# ESP32-C3_V01.net
KiCad netlist of a schematic drawn in Altium Designer
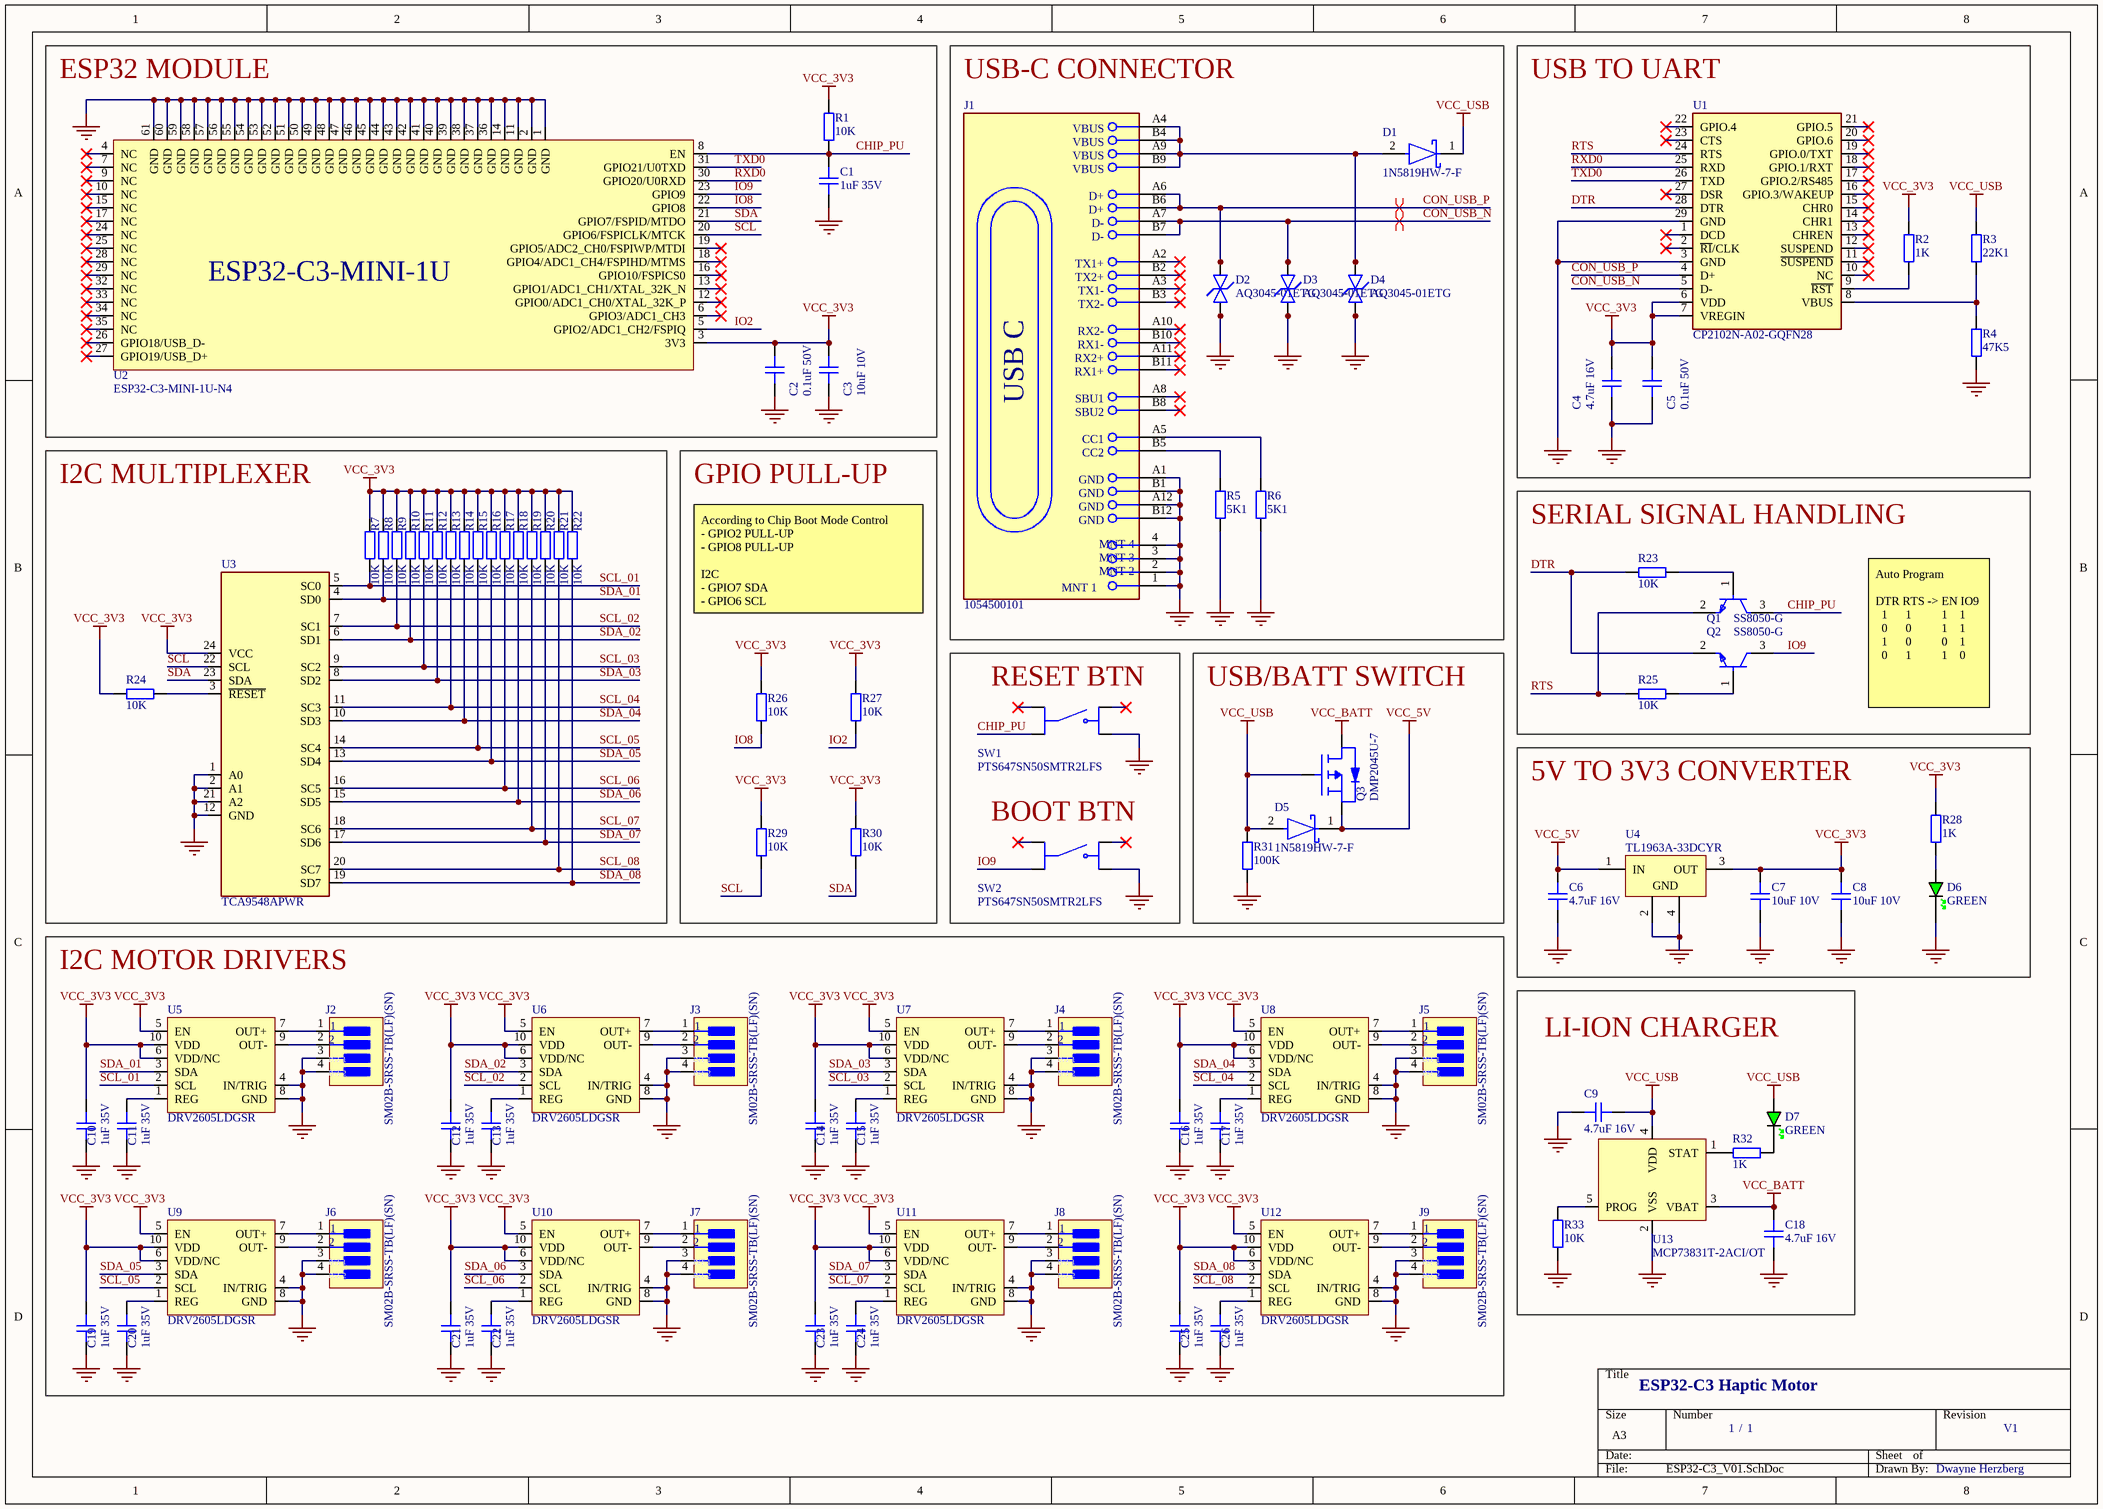
[diagram p0: ESP32-C3_V01.SchDoc]

(export (version "E")
  (design (tool "Eeschema 10.0.6"))
  (components
    (comp (ref "C1")
      (value "1uF 35V")
      (footprint "CAP_0402")
      (description "CAP CER 1UF 35V X5R 0402")
      (fields
        (field (name "MANUFACTURER") "Samsung")
        (field (name "MANUFACTURER PART NUMBER") "CL05A105KL5NRNC")
      )
      (libsource (lib "ESP32-C3") (part "CL05A105KL5NRNC"))
    )
    (comp (ref "C2")
      (value "0.1uF 50V")
      (footprint "CAP_0402")
      (description "CAP CER 0.1UF 50V X7R 0402")
      (fields
        (field (name "MANUFACTURER") "Samsung")
        (field (name "MANUFACTURER PART NUMBER") "CL05B104KB54PNC")
      )
      (libsource (lib "ESP32-C3") (part "CL05B104KB54PNC"))
    )
    (comp (ref "C3")
      (value "10uF 10V")
      (footprint "CAP_0402")
      (description "CAP CER 10UF 10V X5R 0402")
      (fields
        (field (name "MANUFACTURER") "Samsung")
        (field (name "MANUFACTURER PART NUMBER") "CL05A106MP8NUB8")
      )
      (libsource (lib "ESP32-C3") (part "CL05A106MP8NUB8"))
    )
    (comp (ref "C4")
      (value "4.7uF 16V")
      (footprint "CAP_0402")
      (description "CAP CER 4.7UF 16V X5R 0402")
      (fields
        (field (name "MANUFACTURER") "Samsung")
        (field (name "MANUFACTURER PART NUMBER") "CL05A475MO5NUNC")
      )
      (libsource (lib "ESP32-C3") (part "CL05A475MO5NUNC"))
    )
    (comp (ref "C5")
      (value "0.1uF 50V")
      (footprint "CAP_0402")
      (description "CAP CER 0.1UF 50V X7R 0402")
      (fields
        (field (name "MANUFACTURER") "Samsung")
        (field (name "MANUFACTURER PART NUMBER") "CL05B104KB54PNC")
      )
      (libsource (lib "ESP32-C3") (part "CL05B104KB54PNC"))
    )
    (comp (ref "C6")
      (value "4.7uF 16V")
      (footprint "CAP_0402")
      (description "CAP CER 4.7UF 16V X5R 0402")
      (fields
        (field (name "MANUFACTURER") "Samsung")
        (field (name "MANUFACTURER PART NUMBER") "CL05A475MO5NUNC")
      )
      (libsource (lib "ESP32-C3") (part "CL05A475MO5NUNC"))
    )
    (comp (ref "C7")
      (value "10uF 10V")
      (footprint "CAP_0402")
      (description "CAP CER 10UF 10V X5R 0402")
      (fields
        (field (name "MANUFACTURER") "Samsung")
        (field (name "MANUFACTURER PART NUMBER") "CL05A106MP8NUB8")
      )
      (libsource (lib "ESP32-C3") (part "CL05A106MP8NUB8"))
    )
    (comp (ref "C8")
      (value "10uF 10V")
      (footprint "CAP_0402")
      (description "CAP CER 10UF 10V X5R 0402")
      (fields
        (field (name "MANUFACTURER") "Samsung")
        (field (name "MANUFACTURER PART NUMBER") "CL05A106MP8NUB8")
      )
      (libsource (lib "ESP32-C3") (part "CL05A106MP8NUB8"))
    )
    (comp (ref "C9")
      (value "4.7uF 16V")
      (footprint "CAP_0402")
      (description "CAP CER 4.7UF 16V X5R 0402")
      (fields
        (field (name "MANUFACTURER") "Samsung")
        (field (name "MANUFACTURER PART NUMBER") "CL05A475MO5NUNC")
      )
      (libsource (lib "ESP32-C3") (part "CL05A475MO5NUNC"))
    )
    (comp (ref "C10")
      (value "1uF 35V")
      (footprint "CAP_0402")
      (description "CAP CER 1UF 35V X5R 0402")
      (fields
        (field (name "MANUFACTURER") "Samsung")
        (field (name "MANUFACTURER PART NUMBER") "CL05A105KL5NRNC")
      )
      (libsource (lib "ESP32-C3") (part "CL05A105KL5NRNC"))
    )
    (comp (ref "C11")
      (value "1uF 35V")
      (footprint "CAP_0402")
      (description "CAP CER 1UF 35V X5R 0402")
      (fields
        (field (name "MANUFACTURER") "Samsung")
        (field (name "MANUFACTURER PART NUMBER") "CL05A105KL5NRNC")
      )
      (libsource (lib "ESP32-C3") (part "CL05A105KL5NRNC"))
    )
    (comp (ref "C12")
      (value "1uF 35V")
      (footprint "CAP_0402")
      (description "CAP CER 1UF 35V X5R 0402")
      (fields
        (field (name "MANUFACTURER") "Samsung")
        (field (name "MANUFACTURER PART NUMBER") "CL05A105KL5NRNC")
      )
      (libsource (lib "ESP32-C3") (part "CL05A105KL5NRNC"))
    )
    (comp (ref "C13")
      (value "1uF 35V")
      (footprint "CAP_0402")
      (description "CAP CER 1UF 35V X5R 0402")
      (fields
        (field (name "MANUFACTURER") "Samsung")
        (field (name "MANUFACTURER PART NUMBER") "CL05A105KL5NRNC")
      )
      (libsource (lib "ESP32-C3") (part "CL05A105KL5NRNC"))
    )
    (comp (ref "C14")
      (value "1uF 35V")
      (footprint "CAP_0402")
      (description "CAP CER 1UF 35V X5R 0402")
      (fields
        (field (name "MANUFACTURER") "Samsung")
        (field (name "MANUFACTURER PART NUMBER") "CL05A105KL5NRNC")
      )
      (libsource (lib "ESP32-C3") (part "CL05A105KL5NRNC"))
    )
    (comp (ref "C15")
      (value "1uF 35V")
      (footprint "CAP_0402")
      (description "CAP CER 1UF 35V X5R 0402")
      (fields
        (field (name "MANUFACTURER") "Samsung")
        (field (name "MANUFACTURER PART NUMBER") "CL05A105KL5NRNC")
      )
      (libsource (lib "ESP32-C3") (part "CL05A105KL5NRNC"))
    )
    (comp (ref "C16")
      (value "1uF 35V")
      (footprint "CAP_0402")
      (description "CAP CER 1UF 35V X5R 0402")
      (fields
        (field (name "MANUFACTURER") "Samsung")
        (field (name "MANUFACTURER PART NUMBER") "CL05A105KL5NRNC")
      )
      (libsource (lib "ESP32-C3") (part "CL05A105KL5NRNC"))
    )
    (comp (ref "C17")
      (value "1uF 35V")
      (footprint "CAP_0402")
      (description "CAP CER 1UF 35V X5R 0402")
      (fields
        (field (name "MANUFACTURER") "Samsung")
        (field (name "MANUFACTURER PART NUMBER") "CL05A105KL5NRNC")
      )
      (libsource (lib "ESP32-C3") (part "CL05A105KL5NRNC"))
    )
    (comp (ref "C18")
      (value "4.7uF 16V")
      (footprint "CAP_0402")
      (description "CAP CER 4.7UF 16V X5R 0402")
      (fields
        (field (name "MANUFACTURER") "Samsung")
        (field (name "MANUFACTURER PART NUMBER") "CL05A475MO5NUNC")
      )
      (libsource (lib "ESP32-C3") (part "CL05A475MO5NUNC"))
    )
    (comp (ref "C19")
      (value "1uF 35V")
      (footprint "CAP_0402")
      (description "CAP CER 1UF 35V X5R 0402")
      (fields
        (field (name "MANUFACTURER") "Samsung")
        (field (name "MANUFACTURER PART NUMBER") "CL05A105KL5NRNC")
      )
      (libsource (lib "ESP32-C3") (part "CL05A105KL5NRNC"))
    )
    (comp (ref "C20")
      (value "1uF 35V")
      (footprint "CAP_0402")
      (description "CAP CER 1UF 35V X5R 0402")
      (fields
        (field (name "MANUFACTURER") "Samsung")
        (field (name "MANUFACTURER PART NUMBER") "CL05A105KL5NRNC")
      )
      (libsource (lib "ESP32-C3") (part "CL05A105KL5NRNC"))
    )
    (comp (ref "C21")
      (value "1uF 35V")
      (footprint "CAP_0402")
      (description "CAP CER 1UF 35V X5R 0402")
      (fields
        (field (name "MANUFACTURER") "Samsung")
        (field (name "MANUFACTURER PART NUMBER") "CL05A105KL5NRNC")
      )
      (libsource (lib "ESP32-C3") (part "CL05A105KL5NRNC"))
    )
    (comp (ref "C22")
      (value "1uF 35V")
      (footprint "CAP_0402")
      (description "CAP CER 1UF 35V X5R 0402")
      (fields
        (field (name "MANUFACTURER") "Samsung")
        (field (name "MANUFACTURER PART NUMBER") "CL05A105KL5NRNC")
      )
      (libsource (lib "ESP32-C3") (part "CL05A105KL5NRNC"))
    )
    (comp (ref "C23")
      (value "1uF 35V")
      (footprint "CAP_0402")
      (description "CAP CER 1UF 35V X5R 0402")
      (fields
        (field (name "MANUFACTURER") "Samsung")
        (field (name "MANUFACTURER PART NUMBER") "CL05A105KL5NRNC")
      )
      (libsource (lib "ESP32-C3") (part "CL05A105KL5NRNC"))
    )
    (comp (ref "C24")
      (value "1uF 35V")
      (footprint "CAP_0402")
      (description "CAP CER 1UF 35V X5R 0402")
      (fields
        (field (name "MANUFACTURER") "Samsung")
        (field (name "MANUFACTURER PART NUMBER") "CL05A105KL5NRNC")
      )
      (libsource (lib "ESP32-C3") (part "CL05A105KL5NRNC"))
    )
    (comp (ref "C25")
      (value "1uF 35V")
      (footprint "CAP_0402")
      (description "CAP CER 1UF 35V X5R 0402")
      (fields
        (field (name "MANUFACTURER") "Samsung")
        (field (name "MANUFACTURER PART NUMBER") "CL05A105KL5NRNC")
      )
      (libsource (lib "ESP32-C3") (part "CL05A105KL5NRNC"))
    )
    (comp (ref "C26")
      (value "1uF 35V")
      (footprint "CAP_0402")
      (description "CAP CER 1UF 35V X5R 0402")
      (fields
        (field (name "MANUFACTURER") "Samsung")
        (field (name "MANUFACTURER PART NUMBER") "CL05A105KL5NRNC")
      )
      (libsource (lib "ESP32-C3") (part "CL05A105KL5NRNC"))
    )
    (comp (ref "D1")
      (value "1N5819HW-7-F")
      (footprint "FP-SOD123-IPC_B")
      (description "DIODE SCHOTTKY 40V 1A SOD123")
      (fields (field (name "MANUFACTURER") "Diodes") (field (name "JLCPCB PART") "C82544"))
      (libsource (lib "ESP32-C3") (part "1N5819HW-7-F"))
    )
    (comp (ref "D2")
      (value "AQ3045-01ETG")
      (footprint "SP353001ETG")
      (description "TVS DIODE 5.3VWM 12VC SOD882")
      (fields (field (name "MANUFACTURER") "Littelfuse") (field (name "JLCPCB PART") "C3710326"))
      (libsource (lib "ESP32-C3") (part "AQ3045-01ETG"))
    )
    (comp (ref "D3")
      (value "AQ3045-01ETG")
      (footprint "SP353001ETG")
      (description "TVS DIODE 5.3VWM 12VC SOD882")
      (fields (field (name "MANUFACTURER") "Littelfuse") (field (name "JLCPCB PART") "C3710326"))
      (libsource (lib "ESP32-C3") (part "AQ3045-01ETG"))
    )
    (comp (ref "D4")
      (value "AQ3045-01ETG")
      (footprint "SP353001ETG")
      (description "TVS DIODE 5.3VWM 12VC SOD882")
      (fields (field (name "MANUFACTURER") "Littelfuse") (field (name "JLCPCB PART") "C3710326"))
      (libsource (lib "ESP32-C3") (part "AQ3045-01ETG"))
    )
    (comp (ref "D5")
      (value "1N5819HW-7-F")
      (footprint "FP-SOD123-IPC_B")
      (description "DIODE SCHOTTKY 40V 1A SOD123")
      (fields (field (name "MANUFACTURER") "Diodes") (field (name "JLCPCB PART") "C82544"))
      (libsource (lib "ESP32-C3") (part "1N5819HW-7-F"))
    )
    (comp (ref "D6")
      (value "GREEN")
      (footprint "LED_0603_GREEN")
      (description "LED GREEN CLEAR 0603 SMD")
      (fields
        (field (name "MANUFACTURER") "Wurth Electronics")
        (field (name "MANUFACTURER PART NUMBER") "150060GS75000")
      )
      (libsource (lib "ESP32-C3") (part "150060GS75000"))
    )
    (comp (ref "D7")
      (value "GREEN")
      (footprint "LED_0603_GREEN")
      (description "LED GREEN CLEAR 0603 SMD")
      (fields
        (field (name "MANUFACTURER") "Wurth Electronics")
        (field (name "MANUFACTURER PART NUMBER") "150060GS75000")
      )
      (libsource (lib "ESP32-C3") (part "150060GS75000"))
    )
    (comp (ref "J1")
      (value "1054500101")
      (footprint "FP-1054500101-MFG")
      (description "CONN RCP USB3.1 TYPEC 24P SMD RA")
      (fields
        (field (name "MANUFACTURER") "Molex")
        (field (name "OCTOPART") "https://octopart.com/105450-0101-molex-68082325")
      )
      (libsource (lib "ESP32-C3") (part "CMP-04767-000004-1"))
    )
    (comp (ref "J2")
      (value "SM02B-SRSS-TB(LF)(SN)")
      (footprint "FP-SM02B-SRSS-TB_LF_SN-MFG")
      (description "CONN HEADER SMD R/A 2POS 1MM")
      (fields (field (name "MANUFACTURER") "JST") (field (name "JLCPCB PART") "C160402"))
      (libsource (lib "ESP32-C3") (part "SM02B-SRSS-TB(LF)(SN)"))
    )
    (comp (ref "J3")
      (value "SM02B-SRSS-TB(LF)(SN)")
      (footprint "FP-SM02B-SRSS-TB_LF_SN-MFG")
      (description "CONN HEADER SMD R/A 2POS 1MM")
      (fields (field (name "MANUFACTURER") "JST") (field (name "JLCPCB PART") "C160402"))
      (libsource (lib "ESP32-C3") (part "SM02B-SRSS-TB(LF)(SN)"))
    )
    (comp (ref "J4")
      (value "SM02B-SRSS-TB(LF)(SN)")
      (footprint "FP-SM02B-SRSS-TB_LF_SN-MFG")
      (description "CONN HEADER SMD R/A 2POS 1MM")
      (fields (field (name "MANUFACTURER") "JST") (field (name "JLCPCB PART") "C160402"))
      (libsource (lib "ESP32-C3") (part "SM02B-SRSS-TB(LF)(SN)"))
    )
    (comp (ref "J5")
      (value "SM02B-SRSS-TB(LF)(SN)")
      (footprint "FP-SM02B-SRSS-TB_LF_SN-MFG")
      (description "CONN HEADER SMD R/A 2POS 1MM")
      (fields (field (name "MANUFACTURER") "JST") (field (name "JLCPCB PART") "C160402"))
      (libsource (lib "ESP32-C3") (part "SM02B-SRSS-TB(LF)(SN)"))
    )
    (comp (ref "J6")
      (value "SM02B-SRSS-TB(LF)(SN)")
      (footprint "FP-SM02B-SRSS-TB_LF_SN-MFG")
      (description "CONN HEADER SMD R/A 2POS 1MM")
      (fields (field (name "MANUFACTURER") "JST") (field (name "JLCPCB PART") "C160402"))
      (libsource (lib "ESP32-C3") (part "SM02B-SRSS-TB(LF)(SN)"))
    )
    (comp (ref "J7")
      (value "SM02B-SRSS-TB(LF)(SN)")
      (footprint "FP-SM02B-SRSS-TB_LF_SN-MFG")
      (description "CONN HEADER SMD R/A 2POS 1MM")
      (fields (field (name "MANUFACTURER") "JST") (field (name "JLCPCB PART") "C160402"))
      (libsource (lib "ESP32-C3") (part "SM02B-SRSS-TB(LF)(SN)"))
    )
    (comp (ref "J8")
      (value "SM02B-SRSS-TB(LF)(SN)")
      (footprint "FP-SM02B-SRSS-TB_LF_SN-MFG")
      (description "CONN HEADER SMD R/A 2POS 1MM")
      (fields (field (name "MANUFACTURER") "JST") (field (name "JLCPCB PART") "C160402"))
      (libsource (lib "ESP32-C3") (part "SM02B-SRSS-TB(LF)(SN)"))
    )
    (comp (ref "J9")
      (value "SM02B-SRSS-TB(LF)(SN)")
      (footprint "FP-SM02B-SRSS-TB_LF_SN-MFG")
      (description "CONN HEADER SMD R/A 2POS 1MM")
      (fields (field (name "MANUFACTURER") "JST") (field (name "JLCPCB PART") "C160402"))
      (libsource (lib "ESP32-C3") (part "SM02B-SRSS-TB(LF)(SN)"))
    )
    (comp (ref "Q1")
      (value "SS8050-G")
      (footprint "FP-SS8050-G-IPC_B")
      (description "TRANS NPN 25V 1.5A SOT-23-3")
      (fields (field (name "MANUFACTURER") "Comchip") (field (name "JLCPCB PART") "C3199946"))
      (libsource (lib "ESP32-C3") (part "SS8050-G"))
    )
    (comp (ref "Q2")
      (value "SS8050-G")
      (footprint "FP-SS8050-G-IPC_B")
      (description "TRANS NPN 25V 1.5A SOT-23-3")
      (fields (field (name "MANUFACTURER") "Comchip") (field (name "JLCPCB PART") "C3199946"))
      (libsource (lib "ESP32-C3") (part "SS8050-G"))
    )
    (comp (ref "Q3")
      (value "DMP2045U-7")
      (footprint "SOT96P240X115-3N")
      (description "MOSFET P-CH 20V 4.3A SOT23")
      (fields (field (name "MANUFACTURER") "Diodes") (field (name "JLCPCB PART") "C459541"))
      (libsource (lib "ESP32-C3") (part "DMP2045U-7"))
    )
    (comp (ref "R1")
      (value "10K")
      (footprint "RES_0402")
      (description "RES SMD 10K OHM 1% 1/16W 0402")
      (fields
        (field (name "MANUFACTURER") "Yageo")
        (field (name "MANUFACTURER PART NUMBER") "AC0402FR-0710KL")
      )
      (libsource (lib "ESP32-C3") (part "AC0402FR-0710KL"))
    )
    (comp (ref "R2")
      (value "1K")
      (footprint "RES_0402")
      (description "RES 1K OHM 5% 1/16W 0402")
      (fields
        (field (name "MANUFACTURER") "Yageo")
        (field (name "MANUFACTURER PART NUMBER") "RC0402JR-071KL")
      )
      (libsource (lib "ESP32-C3") (part "RC0402JR-071KL"))
    )
    (comp (ref "R3")
      (value "22K1")
      (footprint "RES_0402")
      (description "RES 22.1K OHM 1% 1/16W 0402")
      (fields
        (field (name "MANUFACTURER") "Yageo")
        (field (name "MANUFACTURER PART NUMBER") "RC0402FR-0722K1L")
      )
      (libsource (lib "ESP32-C3") (part "RC0402FR-0722K1L"))
    )
    (comp (ref "R4")
      (value "47K5")
      (footprint "RES_0402")
      (description "RES 47.5K OHM 1% 1/16W 0402")
      (fields
        (field (name "MANUFACTURER") "Yageo")
        (field (name "MANUFACTURER PART NUMBER") "RC0402FR-0747K5L")
      )
      (libsource (lib "ESP32-C3") (part "RC0402FR-0747K5L"))
    )
    (comp (ref "R5")
      (value "5K1")
      (footprint "RES_0402")
      (description "RES SMD 5.1K OHM 1% 1/16W 0402")
      (fields
        (field (name "MANUFACTURER") "Yageo")
        (field (name "MANUFACTURER PART NUMBER") "AC0402FR-075K1L")
      )
      (libsource (lib "ESP32-C3") (part "AC0402FR-075K1L"))
    )
    (comp (ref "R6")
      (value "5K1")
      (footprint "RES_0402")
      (description "RES SMD 5.1K OHM 1% 1/16W 0402")
      (fields
        (field (name "MANUFACTURER") "Yageo")
        (field (name "MANUFACTURER PART NUMBER") "AC0402FR-075K1L")
      )
      (libsource (lib "ESP32-C3") (part "AC0402FR-075K1L"))
    )
    (comp (ref "R7")
      (value "10K")
      (footprint "RES_0402")
      (description "RES SMD 10K OHM 1% 1/16W 0402")
      (fields
        (field (name "MANUFACTURER") "Yageo")
        (field (name "MANUFACTURER PART NUMBER") "AC0402FR-0710KL")
      )
      (libsource (lib "ESP32-C3") (part "AC0402FR-0710KL"))
    )
    (comp (ref "R8")
      (value "10K")
      (footprint "RES_0402")
      (description "RES SMD 10K OHM 1% 1/16W 0402")
      (fields
        (field (name "MANUFACTURER") "Yageo")
        (field (name "MANUFACTURER PART NUMBER") "AC0402FR-0710KL")
      )
      (libsource (lib "ESP32-C3") (part "AC0402FR-0710KL"))
    )
    (comp (ref "R9")
      (value "10K")
      (footprint "RES_0402")
      (description "RES SMD 10K OHM 1% 1/16W 0402")
      (fields
        (field (name "MANUFACTURER") "Yageo")
        (field (name "MANUFACTURER PART NUMBER") "AC0402FR-0710KL")
      )
      (libsource (lib "ESP32-C3") (part "AC0402FR-0710KL"))
    )
    (comp (ref "R10")
      (value "10K")
      (footprint "RES_0402")
      (description "RES SMD 10K OHM 1% 1/16W 0402")
      (fields
        (field (name "MANUFACTURER") "Yageo")
        (field (name "MANUFACTURER PART NUMBER") "AC0402FR-0710KL")
      )
      (libsource (lib "ESP32-C3") (part "AC0402FR-0710KL"))
    )
    (comp (ref "R11")
      (value "10K")
      (footprint "RES_0402")
      (description "RES SMD 10K OHM 1% 1/16W 0402")
      (fields
        (field (name "MANUFACTURER") "Yageo")
        (field (name "MANUFACTURER PART NUMBER") "AC0402FR-0710KL")
      )
      (libsource (lib "ESP32-C3") (part "AC0402FR-0710KL"))
    )
    (comp (ref "R12")
      (value "10K")
      (footprint "RES_0402")
      (description "RES SMD 10K OHM 1% 1/16W 0402")
      (fields
        (field (name "MANUFACTURER") "Yageo")
        (field (name "MANUFACTURER PART NUMBER") "AC0402FR-0710KL")
      )
      (libsource (lib "ESP32-C3") (part "AC0402FR-0710KL"))
    )
    (comp (ref "R13")
      (value "10K")
      (footprint "RES_0402")
      (description "RES SMD 10K OHM 1% 1/16W 0402")
      (fields
        (field (name "MANUFACTURER") "Yageo")
        (field (name "MANUFACTURER PART NUMBER") "AC0402FR-0710KL")
      )
      (libsource (lib "ESP32-C3") (part "AC0402FR-0710KL"))
    )
    (comp (ref "R14")
      (value "10K")
      (footprint "RES_0402")
      (description "RES SMD 10K OHM 1% 1/16W 0402")
      (fields
        (field (name "MANUFACTURER") "Yageo")
        (field (name "MANUFACTURER PART NUMBER") "AC0402FR-0710KL")
      )
      (libsource (lib "ESP32-C3") (part "AC0402FR-0710KL"))
    )
    (comp (ref "R15")
      (value "10K")
      (footprint "RES_0402")
      (description "RES SMD 10K OHM 1% 1/16W 0402")
      (fields
        (field (name "MANUFACTURER") "Yageo")
        (field (name "MANUFACTURER PART NUMBER") "AC0402FR-0710KL")
      )
      (libsource (lib "ESP32-C3") (part "AC0402FR-0710KL"))
    )
    (comp (ref "R16")
      (value "10K")
      (footprint "RES_0402")
      (description "RES SMD 10K OHM 1% 1/16W 0402")
      (fields
        (field (name "MANUFACTURER") "Yageo")
        (field (name "MANUFACTURER PART NUMBER") "AC0402FR-0710KL")
      )
      (libsource (lib "ESP32-C3") (part "AC0402FR-0710KL"))
    )
    (comp (ref "R17")
      (value "10K")
      (footprint "RES_0402")
      (description "RES SMD 10K OHM 1% 1/16W 0402")
      (fields
        (field (name "MANUFACTURER") "Yageo")
        (field (name "MANUFACTURER PART NUMBER") "AC0402FR-0710KL")
      )
      (libsource (lib "ESP32-C3") (part "AC0402FR-0710KL"))
    )
    (comp (ref "R18")
      (value "10K")
      (footprint "RES_0402")
      (description "RES SMD 10K OHM 1% 1/16W 0402")
      (fields
        (field (name "MANUFACTURER") "Yageo")
        (field (name "MANUFACTURER PART NUMBER") "AC0402FR-0710KL")
      )
      (libsource (lib "ESP32-C3") (part "AC0402FR-0710KL"))
    )
    (comp (ref "R19")
      (value "10K")
      (footprint "RES_0402")
      (description "RES SMD 10K OHM 1% 1/16W 0402")
      (fields
        (field (name "MANUFACTURER") "Yageo")
        (field (name "MANUFACTURER PART NUMBER") "AC0402FR-0710KL")
      )
      (libsource (lib "ESP32-C3") (part "AC0402FR-0710KL"))
    )
    (comp (ref "R20")
      (value "10K")
      (footprint "RES_0402")
      (description "RES SMD 10K OHM 1% 1/16W 0402")
      (fields
        (field (name "MANUFACTURER") "Yageo")
        (field (name "MANUFACTURER PART NUMBER") "AC0402FR-0710KL")
      )
      (libsource (lib "ESP32-C3") (part "AC0402FR-0710KL"))
    )
    (comp (ref "R21")
      (value "10K")
      (footprint "RES_0402")
      (description "RES SMD 10K OHM 1% 1/16W 0402")
      (fields
        (field (name "MANUFACTURER") "Yageo")
        (field (name "MANUFACTURER PART NUMBER") "AC0402FR-0710KL")
      )
      (libsource (lib "ESP32-C3") (part "AC0402FR-0710KL"))
    )
    (comp (ref "R22")
      (value "10K")
      (footprint "RES_0402")
      (description "RES SMD 10K OHM 1% 1/16W 0402")
      (fields
        (field (name "MANUFACTURER") "Yageo")
        (field (name "MANUFACTURER PART NUMBER") "AC0402FR-0710KL")
      )
      (libsource (lib "ESP32-C3") (part "AC0402FR-0710KL"))
    )
    (comp (ref "R23")
      (value "10K")
      (footprint "RES_0402")
      (description "RES SMD 10K OHM 1% 1/16W 0402")
      (fields
        (field (name "MANUFACTURER") "Yageo")
        (field (name "MANUFACTURER PART NUMBER") "AC0402FR-0710KL")
      )
      (libsource (lib "ESP32-C3") (part "AC0402FR-0710KL"))
    )
    (comp (ref "R24")
      (value "10K")
      (footprint "RES_0402")
      (description "RES SMD 10K OHM 1% 1/16W 0402")
      (fields
        (field (name "MANUFACTURER") "Yageo")
        (field (name "MANUFACTURER PART NUMBER") "AC0402FR-0710KL")
      )
      (libsource (lib "ESP32-C3") (part "AC0402FR-0710KL"))
    )
    (comp (ref "R25")
      (value "10K")
      (footprint "RES_0402")
      (description "RES SMD 10K OHM 1% 1/16W 0402")
      (fields
        (field (name "MANUFACTURER") "Yageo")
        (field (name "MANUFACTURER PART NUMBER") "AC0402FR-0710KL")
      )
      (libsource (lib "ESP32-C3") (part "AC0402FR-0710KL"))
    )
    (comp (ref "R26")
      (value "10K")
      (footprint "RES_0402")
      (description "RES SMD 10K OHM 1% 1/16W 0402")
      (fields
        (field (name "MANUFACTURER") "Yageo")
        (field (name "MANUFACTURER PART NUMBER") "AC0402FR-0710KL")
      )
      (libsource (lib "ESP32-C3") (part "AC0402FR-0710KL"))
    )
    (comp (ref "R27")
      (value "10K")
      (footprint "RES_0402")
      (description "RES SMD 10K OHM 1% 1/16W 0402")
      (fields
        (field (name "MANUFACTURER") "Yageo")
        (field (name "MANUFACTURER PART NUMBER") "AC0402FR-0710KL")
      )
      (libsource (lib "ESP32-C3") (part "AC0402FR-0710KL"))
    )
    (comp (ref "R28")
      (value "1K")
      (footprint "RES_0402")
      (description "RES 1K OHM 5% 1/16W 0402")
      (fields
        (field (name "MANUFACTURER") "Yageo")
        (field (name "MANUFACTURER PART NUMBER") "RC0402JR-071KL")
      )
      (libsource (lib "ESP32-C3") (part "RC0402JR-071KL"))
    )
    (comp (ref "R29")
      (value "10K")
      (footprint "RES_0402")
      (description "RES SMD 10K OHM 1% 1/16W 0402")
      (fields
        (field (name "MANUFACTURER") "Yageo")
        (field (name "MANUFACTURER PART NUMBER") "AC0402FR-0710KL")
      )
      (libsource (lib "ESP32-C3") (part "AC0402FR-0710KL"))
    )
    (comp (ref "R30")
      (value "10K")
      (footprint "RES_0402")
      (description "RES SMD 10K OHM 1% 1/16W 0402")
      (fields
        (field (name "MANUFACTURER") "Yageo")
        (field (name "MANUFACTURER PART NUMBER") "AC0402FR-0710KL")
      )
      (libsource (lib "ESP32-C3") (part "AC0402FR-0710KL"))
    )
    (comp (ref "R31")
      (value "100K")
      (footprint "RES_0402")
      (description "RES 100K OHM 1% 1/16W 0402")
      (fields
        (field (name "MANUFACTURER") "Yageo")
        (field (name "MANUFACTURER PART NUMBER") "RC0402FR-07100KL")
      )
      (libsource (lib "ESP32-C3") (part "RC0402FR-07100KL"))
    )
    (comp (ref "R32")
      (value "1K")
      (footprint "RES_0402")
      (description "RES 1K OHM 5% 1/16W 0402")
      (fields
        (field (name "MANUFACTURER") "Yageo")
        (field (name "MANUFACTURER PART NUMBER") "RC0402JR-071KL")
      )
      (libsource (lib "ESP32-C3") (part "RC0402JR-071KL"))
    )
    (comp (ref "R33")
      (value "10K")
      (footprint "RES_0402")
      (description "RES SMD 10K OHM 1% 1/16W 0402")
      (fields
        (field (name "MANUFACTURER") "Yageo")
        (field (name "MANUFACTURER PART NUMBER") "AC0402FR-0710KL")
      )
      (libsource (lib "ESP32-C3") (part "AC0402FR-0710KL"))
    )
    (comp (ref "SW1")
      (value "PTS647SN50SMTR2LFS")
      (footprint "PTS 647 SN50 SMTR2 LFS")
      (description "SWITCH TACTILE SPST-NO 0.05A 12V")
      (fields (field (name "MANUFACTURER") "ITT C&K") (field (name "JLCPCB PART") "C2799414"))
      (libsource (lib "ESP32-C3") (part "PTS647SN50SMTR2LFS"))
    )
    (comp (ref "SW2")
      (value "PTS647SN50SMTR2LFS")
      (footprint "PTS 647 SN50 SMTR2 LFS")
      (description "SWITCH TACTILE SPST-NO 0.05A 12V")
      (fields (field (name "MANUFACTURER") "ITT C&K") (field (name "JLCPCB PART") "C2799414"))
      (libsource (lib "ESP32-C3") (part "PTS647SN50SMTR2LFS"))
    )
    (comp (ref "U1")
      (value "CP2102N-A02-GQFN28")
      (footprint "FP-CP2102N-A02-GQFN28-IPC_B")
      (description "IC USB TO UART BRIDGE QFN28")
      (fields (field (name "MANUFACTURER") "Silicon Labs") (field (name "JLCPCB PART") "C1550553"))
      (libsource (lib "ESP32-C3") (part "CP2102N-A02-GQFN28"))
    )
    (comp (ref "U2")
      (value "ESP32-C3-MINI-1U-N4")
      (footprint "ESP32-C3-MINI-1U_EXP")
      (description "RF TXRX MOD BT WIFIU.FL SMD")
      (fields (field (name "MANUFACTURER") "Espressif Systems") (field (name "JLCPCB PART") "C2911374"))
      (libsource (lib "ESP32-C3") (part "ESP32-C3-MINI-1U-N4"))
    )
    (comp (ref "U3")
      (value "TCA9548APWR")
      (footprint "FP-PW0024A-IPC_B")
      (description "IC BUS SWITCH 1 X 8:1 24TSSOP")
      (fields (field (name "MANUFACTURER") "Texas Instruments") (field (name "JLCPCB PART") "C130026"))
      (libsource (lib "ESP32-C3") (part "TCA9548APWR"))
    )
    (comp (ref "U4")
      (value "TL1963A-33DCYR")
      (footprint "DCY0004A_L")
      (fields (field (name "MANUFACTURER") "Texas Instruments") (field (name "JLCPCB PART") "C181262"))
      (libsource (lib "ESP32-C3") (part "TL1963A-33DCYR"))
    )
    (comp (ref "U5")
      (value "DRV2605LDGSR")
      (footprint "FP-DGS0010A-IPC_B")
      (description "IC MOTOR DRIVER 2V-5.5V 10VSSOP")
      (fields (field (name "MANUFACTURER") "Texas Instruments") (field (name "JLCPCB PART") "C527464"))
      (libsource (lib "ESP32-C3") (part "DRV2605LDGSR"))
    )
    (comp (ref "U6")
      (value "DRV2605LDGSR")
      (footprint "FP-DGS0010A-IPC_B")
      (description "IC MOTOR DRIVER 2V-5.5V 10VSSOP")
      (fields (field (name "MANUFACTURER") "Texas Instruments") (field (name "JLCPCB PART") "C527464"))
      (libsource (lib "ESP32-C3") (part "DRV2605LDGSR"))
    )
    (comp (ref "U7")
      (value "DRV2605LDGSR")
      (footprint "FP-DGS0010A-IPC_B")
      (description "IC MOTOR DRIVER 2V-5.5V 10VSSOP")
      (fields (field (name "MANUFACTURER") "Texas Instruments") (field (name "JLCPCB PART") "C527464"))
      (libsource (lib "ESP32-C3") (part "DRV2605LDGSR"))
    )
    (comp (ref "U8")
      (value "DRV2605LDGSR")
      (footprint "FP-DGS0010A-IPC_B")
      (description "IC MOTOR DRIVER 2V-5.5V 10VSSOP")
      (fields (field (name "MANUFACTURER") "Texas Instruments") (field (name "JLCPCB PART") "C527464"))
      (libsource (lib "ESP32-C3") (part "DRV2605LDGSR"))
    )
    (comp (ref "U9")
      (value "DRV2605LDGSR")
      (footprint "FP-DGS0010A-IPC_B")
      (description "IC MOTOR DRIVER 2V-5.5V 10VSSOP")
      (fields (field (name "MANUFACTURER") "Texas Instruments") (field (name "JLCPCB PART") "C527464"))
      (libsource (lib "ESP32-C3") (part "DRV2605LDGSR"))
    )
    (comp (ref "U10")
      (value "DRV2605LDGSR")
      (footprint "FP-DGS0010A-IPC_B")
      (description "IC MOTOR DRIVER 2V-5.5V 10VSSOP")
      (fields (field (name "MANUFACTURER") "Texas Instruments") (field (name "JLCPCB PART") "C527464"))
      (libsource (lib "ESP32-C3") (part "DRV2605LDGSR"))
    )
    (comp (ref "U11")
      (value "DRV2605LDGSR")
      (footprint "FP-DGS0010A-IPC_B")
      (description "IC MOTOR DRIVER 2V-5.5V 10VSSOP")
      (fields (field (name "MANUFACTURER") "Texas Instruments") (field (name "JLCPCB PART") "C527464"))
      (libsource (lib "ESP32-C3") (part "DRV2605LDGSR"))
    )
    (comp (ref "U12")
      (value "DRV2605LDGSR")
      (footprint "FP-DGS0010A-IPC_B")
      (description "IC MOTOR DRIVER 2V-5.5V 10VSSOP")
      (fields (field (name "MANUFACTURER") "Texas Instruments") (field (name "JLCPCB PART") "C527464"))
      (libsource (lib "ESP32-C3") (part "DRV2605LDGSR"))
    )
    (comp (ref "U13")
      (value "MCP73831T-2ACI/OT")
      (footprint "FP-C04-091-OT-IPC_B")
      (description "IC BATT CNTL LI-ION 1CEL SOT23-5")
      (fields (field (name "MANUFACTURER") "Microchip") (field (name "JLCPCB PART") "C424093"))
      (libsource (lib "ESP32-C3") (part "MCP73831T-2ACI/OT"))
    )
  )
  (nets
    (net (code "1") (name "/CHIP_PU") (class "Default")
      (node (ref "C1") (pin "2") (pinfunction "2_2") (pintype "passive"))
      (node (ref "Q1") (pin "3") (pinfunction "C_3") (pintype "passive"))
      (node (ref "R1") (pin "1") (pinfunction "1_1") (pintype "passive"))
      (node (ref "SW1") (pin "3") (pinfunction "NO_3") (pintype "passive"))
      (node (ref "U2") (pin "8") (pinfunction "EN_8") (pintype "passive"))
    )
    (net (code "2") (name "/CON_USB_N") (class "Default")
      (node (ref "D3") (pin "2") (pinfunction "K_2") (pintype "passive"))
      (node (ref "D3") (pin "K") (pinfunction "K_K") (pintype "passive"))
      (node (ref "J1") (pin "A7") (pinfunction "D-_A7") (pintype "passive"))
      (node (ref "J1") (pin "B7") (pinfunction "D-_B7") (pintype "passive"))
      (node (ref "U1") (pin "5") (pinfunction "D-_5") (pintype "passive"))
    )
    (net (code "3") (name "/CON_USB_P") (class "Default")
      (node (ref "D2") (pin "2") (pinfunction "K_2") (pintype "passive"))
      (node (ref "D2") (pin "K") (pinfunction "K_K") (pintype "passive"))
      (node (ref "J1") (pin "A6") (pinfunction "D+_A6") (pintype "passive"))
      (node (ref "J1") (pin "B6") (pinfunction "D+_B6") (pintype "passive"))
      (node (ref "U1") (pin "4") (pinfunction "D+_4") (pintype "passive"))
    )
    (net (code "4") (name "/DTR") (class "Default")
      (node (ref "Q2") (pin "2") (pinfunction "E_2") (pintype "passive"))
      (node (ref "R23") (pin "2") (pinfunction "2_2") (pintype "passive"))
      (node (ref "U1") (pin "28") (pinfunction "DTR_28") (pintype "passive"))
    )
    (net (code "5") (name "/IO2") (class "Default")
      (node (ref "R27") (pin "1") (pinfunction "1_1") (pintype "passive"))
      (node (ref "U2") (pin "5") (pinfunction "GPIO2/ADC1_CH2/FSPIQ_5") (pintype "passive"))
    )
    (net (code "6") (name "/IO8") (class "Default")
      (node (ref "R26") (pin "1") (pinfunction "1_1") (pintype "passive"))
      (node (ref "U2") (pin "22") (pinfunction "GPIO8_22") (pintype "passive"))
    )
    (net (code "7") (name "/IO9") (class "Default")
      (node (ref "Q2") (pin "3") (pinfunction "C_3") (pintype "passive"))
      (node (ref "SW2") (pin "3") (pinfunction "NO_3") (pintype "passive"))
      (node (ref "U2") (pin "23") (pinfunction "GPIO9_23") (pintype "passive"))
    )
    (net (code "8") (name "/RTS") (class "Default")
      (node (ref "Q1") (pin "2") (pinfunction "E_2") (pintype "passive"))
      (node (ref "R25") (pin "2") (pinfunction "2_2") (pintype "passive"))
      (node (ref "U1") (pin "24") (pinfunction "RTS_24") (pintype "passive"))
    )
    (net (code "9") (name "/RXD0") (class "Default")
      (node (ref "U1") (pin "25") (pinfunction "RXD_25") (pintype "passive"))
      (node (ref "U2") (pin "30") (pinfunction "GPIO20/U0RXD_30") (pintype "passive"))
    )
    (net (code "10") (name "/SCL") (class "Default")
      (node (ref "R29") (pin "1") (pinfunction "1_1") (pintype "passive"))
      (node (ref "U2") (pin "20") (pinfunction "GPIO6/FSPICLK/MTCK_20") (pintype "passive"))
      (node (ref "U3") (pin "22") (pinfunction "SCL_22") (pintype "passive"))
    )
    (net (code "11") (name "/SCL_01") (class "Default")
      (node (ref "R7") (pin "1") (pinfunction "1_1") (pintype "passive"))
      (node (ref "U3") (pin "5") (pinfunction "SC0_5") (pintype "passive"))
      (node (ref "U5") (pin "2") (pinfunction "SCL_2") (pintype "passive"))
    )
    (net (code "12") (name "/SCL_02") (class "Default")
      (node (ref "R9") (pin "1") (pinfunction "1_1") (pintype "passive"))
      (node (ref "U3") (pin "7") (pinfunction "SC1_7") (pintype "passive"))
      (node (ref "U6") (pin "2") (pinfunction "SCL_2") (pintype "passive"))
    )
    (net (code "13") (name "/SCL_03") (class "Default")
      (node (ref "R11") (pin "1") (pinfunction "1_1") (pintype "passive"))
      (node (ref "U3") (pin "9") (pinfunction "SC2_9") (pintype "passive"))
      (node (ref "U7") (pin "2") (pinfunction "SCL_2") (pintype "passive"))
    )
    (net (code "14") (name "/SCL_04") (class "Default")
      (node (ref "R13") (pin "1") (pinfunction "1_1") (pintype "passive"))
      (node (ref "U3") (pin "11") (pinfunction "SC3_11") (pintype "passive"))
      (node (ref "U8") (pin "2") (pinfunction "SCL_2") (pintype "passive"))
    )
    (net (code "15") (name "/SCL_05") (class "Default")
      (node (ref "R15") (pin "1") (pinfunction "1_1") (pintype "passive"))
      (node (ref "U3") (pin "14") (pinfunction "SC4_14") (pintype "passive"))
      (node (ref "U9") (pin "2") (pinfunction "SCL_2") (pintype "passive"))
    )
    (net (code "16") (name "/SCL_06") (class "Default")
      (node (ref "R17") (pin "1") (pinfunction "1_1") (pintype "passive"))
      (node (ref "U10") (pin "2") (pinfunction "SCL_2") (pintype "passive"))
      (node (ref "U3") (pin "16") (pinfunction "SC5_16") (pintype "passive"))
    )
    (net (code "17") (name "/SCL_07") (class "Default")
      (node (ref "R19") (pin "1") (pinfunction "1_1") (pintype "passive"))
      (node (ref "U11") (pin "2") (pinfunction "SCL_2") (pintype "passive"))
      (node (ref "U3") (pin "18") (pinfunction "SC6_18") (pintype "passive"))
    )
    (net (code "18") (name "/SCL_08") (class "Default")
      (node (ref "R21") (pin "1") (pinfunction "1_1") (pintype "passive"))
      (node (ref "U12") (pin "2") (pinfunction "SCL_2") (pintype "passive"))
      (node (ref "U3") (pin "20") (pinfunction "SC7_20") (pintype "passive"))
    )
    (net (code "19") (name "/SDA") (class "Default")
      (node (ref "R30") (pin "1") (pinfunction "1_1") (pintype "passive"))
      (node (ref "U2") (pin "21") (pinfunction "GPIO7/FSPID/MTDO_21") (pintype "passive"))
      (node (ref "U3") (pin "23") (pinfunction "SDA_23") (pintype "passive"))
    )
    (net (code "20") (name "/SDA_01") (class "Default")
      (node (ref "R8") (pin "1") (pinfunction "1_1") (pintype "passive"))
      (node (ref "U3") (pin "4") (pinfunction "SD0_4") (pintype "passive"))
      (node (ref "U5") (pin "3") (pinfunction "SDA_3") (pintype "passive"))
    )
    (net (code "21") (name "/SDA_02") (class "Default")
      (node (ref "R10") (pin "1") (pinfunction "1_1") (pintype "passive"))
      (node (ref "U3") (pin "6") (pinfunction "SD1_6") (pintype "passive"))
      (node (ref "U6") (pin "3") (pinfunction "SDA_3") (pintype "passive"))
    )
    (net (code "22") (name "/SDA_03") (class "Default")
      (node (ref "R12") (pin "1") (pinfunction "1_1") (pintype "passive"))
      (node (ref "U3") (pin "8") (pinfunction "SD2_8") (pintype "passive"))
      (node (ref "U7") (pin "3") (pinfunction "SDA_3") (pintype "passive"))
    )
    (net (code "23") (name "/SDA_04") (class "Default")
      (node (ref "R14") (pin "1") (pinfunction "1_1") (pintype "passive"))
      (node (ref "U3") (pin "10") (pinfunction "SD3_10") (pintype "passive"))
      (node (ref "U8") (pin "3") (pinfunction "SDA_3") (pintype "passive"))
    )
    (net (code "24") (name "/SDA_05") (class "Default")
      (node (ref "R16") (pin "1") (pinfunction "1_1") (pintype "passive"))
      (node (ref "U3") (pin "13") (pinfunction "SD4_13") (pintype "passive"))
      (node (ref "U9") (pin "3") (pinfunction "SDA_3") (pintype "passive"))
    )
    (net (code "25") (name "/SDA_06") (class "Default")
      (node (ref "R18") (pin "1") (pinfunction "1_1") (pintype "passive"))
      (node (ref "U10") (pin "3") (pinfunction "SDA_3") (pintype "passive"))
      (node (ref "U3") (pin "15") (pinfunction "SD5_15") (pintype "passive"))
    )
    (net (code "26") (name "/SDA_07") (class "Default")
      (node (ref "R20") (pin "1") (pinfunction "1_1") (pintype "passive"))
      (node (ref "U11") (pin "3") (pinfunction "SDA_3") (pintype "passive"))
      (node (ref "U3") (pin "17") (pinfunction "SD6_17") (pintype "passive"))
    )
    (net (code "27") (name "/SDA_08") (class "Default")
      (node (ref "R22") (pin "1") (pinfunction "1_1") (pintype "passive"))
      (node (ref "U12") (pin "3") (pinfunction "SDA_3") (pintype "passive"))
      (node (ref "U3") (pin "19") (pinfunction "SD7_19") (pintype "passive"))
    )
    (net (code "28") (name "/TXD0") (class "Default")
      (node (ref "U1") (pin "26") (pinfunction "TXD_26") (pintype "passive"))
      (node (ref "U2") (pin "31") (pinfunction "GPIO21/U0TXD_31") (pintype "passive"))
    )
    (net (code "29") (name "GND") (class "Default")
      (node (ref "C1") (pin "1") (pinfunction "1_1") (pintype "passive"))
      (node (ref "C10") (pin "1") (pinfunction "1_1") (pintype "passive"))
      (node (ref "C11") (pin "1") (pinfunction "1_1") (pintype "passive"))
      (node (ref "C12") (pin "1") (pinfunction "1_1") (pintype "passive"))
      (node (ref "C13") (pin "1") (pinfunction "1_1") (pintype "passive"))
      (node (ref "C14") (pin "1") (pinfunction "1_1") (pintype "passive"))
      (node (ref "C15") (pin "1") (pinfunction "1_1") (pintype "passive"))
      (node (ref "C16") (pin "1") (pinfunction "1_1") (pintype "passive"))
      (node (ref "C17") (pin "1") (pinfunction "1_1") (pintype "passive"))
      (node (ref "C18") (pin "2") (pinfunction "2_2") (pintype "passive"))
      (node (ref "C19") (pin "1") (pinfunction "1_1") (pintype "passive"))
      (node (ref "C2") (pin "1") (pinfunction "1_1") (pintype "passive"))
      (node (ref "C20") (pin "1") (pinfunction "1_1") (pintype "passive"))
      (node (ref "C21") (pin "1") (pinfunction "1_1") (pintype "passive"))
      (node (ref "C22") (pin "1") (pinfunction "1_1") (pintype "passive"))
      (node (ref "C23") (pin "1") (pinfunction "1_1") (pintype "passive"))
      (node (ref "C24") (pin "1") (pinfunction "1_1") (pintype "passive"))
      (node (ref "C25") (pin "1") (pinfunction "1_1") (pintype "passive"))
      (node (ref "C26") (pin "1") (pinfunction "1_1") (pintype "passive"))
      (node (ref "C3") (pin "1") (pinfunction "1_1") (pintype "passive"))
      (node (ref "C4") (pin "1") (pinfunction "1_1") (pintype "passive"))
      (node (ref "C5") (pin "1") (pinfunction "1_1") (pintype "passive"))
      (node (ref "C6") (pin "1") (pinfunction "1_1") (pintype "passive"))
      (node (ref "C7") (pin "1") (pinfunction "1_1") (pintype "passive"))
      (node (ref "C8") (pin "1") (pinfunction "1_1") (pintype "passive"))
      (node (ref "C9") (pin "2") (pinfunction "2_2") (pintype "passive"))
      (node (ref "D2") (pin "1") (pinfunction "A_1") (pintype "passive"))
      (node (ref "D2") (pin "A") (pinfunction "A_A") (pintype "passive"))
      (node (ref "D3") (pin "1") (pinfunction "A_1") (pintype "passive"))
      (node (ref "D3") (pin "A") (pinfunction "A_A") (pintype "passive"))
      (node (ref "D4") (pin "1") (pinfunction "A_1") (pintype "passive"))
      (node (ref "D4") (pin "A") (pinfunction "A_A") (pintype "passive"))
      (node (ref "D6") (pin "K") (pinfunction "K_K") (pintype "passive"))
      (node (ref "J1") (pin "1") (pinfunction "MNT_1_1") (pintype "passive"))
      (node (ref "J1") (pin "2") (pinfunction "MNT_2_2") (pintype "passive"))
      (node (ref "J1") (pin "3") (pinfunction "MNT_3_3") (pintype "passive"))
      (node (ref "J1") (pin "4") (pinfunction "MNT_4_4") (pintype "passive"))
      (node (ref "J1") (pin "A1") (pinfunction "GND_A1") (pintype "passive"))
      (node (ref "J1") (pin "A12") (pinfunction "GND_A12") (pintype "passive"))
      (node (ref "J1") (pin "B1") (pinfunction "GND_B1") (pintype "passive"))
      (node (ref "J1") (pin "B12") (pinfunction "GND_B12") (pintype "passive"))
      (node (ref "J2") (pin "3") (pinfunction "MNT_1_3") (pintype "passive"))
      (node (ref "J2") (pin "4") (pinfunction "MNT_2_4") (pintype "passive"))
      (node (ref "J3") (pin "3") (pinfunction "MNT_1_3") (pintype "passive"))
      (node (ref "J3") (pin "4") (pinfunction "MNT_2_4") (pintype "passive"))
      (node (ref "J4") (pin "3") (pinfunction "MNT_1_3") (pintype "passive"))
      (node (ref "J4") (pin "4") (pinfunction "MNT_2_4") (pintype "passive"))
      (node (ref "J5") (pin "3") (pinfunction "MNT_1_3") (pintype "passive"))
      (node (ref "J5") (pin "4") (pinfunction "MNT_2_4") (pintype "passive"))
      (node (ref "J6") (pin "3") (pinfunction "MNT_1_3") (pintype "passive"))
      (node (ref "J6") (pin "4") (pinfunction "MNT_2_4") (pintype "passive"))
      (node (ref "J7") (pin "3") (pinfunction "MNT_1_3") (pintype "passive"))
      (node (ref "J7") (pin "4") (pinfunction "MNT_2_4") (pintype "passive"))
      (node (ref "J8") (pin "3") (pinfunction "MNT_1_3") (pintype "passive"))
      (node (ref "J8") (pin "4") (pinfunction "MNT_2_4") (pintype "passive"))
      (node (ref "J9") (pin "3") (pinfunction "MNT_1_3") (pintype "passive"))
      (node (ref "J9") (pin "4") (pinfunction "MNT_2_4") (pintype "passive"))
      (node (ref "R31") (pin "1") (pinfunction "1_1") (pintype "passive"))
      (node (ref "R33") (pin "1") (pinfunction "1_1") (pintype "passive"))
      (node (ref "R4") (pin "1") (pinfunction "1_1") (pintype "passive"))
      (node (ref "R5") (pin "1") (pinfunction "1_1") (pintype "passive"))
      (node (ref "R6") (pin "1") (pinfunction "1_1") (pintype "passive"))
      (node (ref "SW1") (pin "4") (pinfunction "NO_4") (pintype "passive"))
      (node (ref "SW2") (pin "4") (pinfunction "NO_4") (pintype "passive"))
      (node (ref "U1") (pin "29") (pinfunction "GND_29") (pintype "passive"))
      (node (ref "U1") (pin "3") (pinfunction "GND_3") (pintype "passive"))
      (node (ref "U10") (pin "4") (pinfunction "IN/TRIG_4") (pintype "passive"))
      (node (ref "U10") (pin "8") (pinfunction "GND_8") (pintype "passive"))
      (node (ref "U11") (pin "4") (pinfunction "IN/TRIG_4") (pintype "passive"))
      (node (ref "U11") (pin "8") (pinfunction "GND_8") (pintype "passive"))
      (node (ref "U12") (pin "4") (pinfunction "IN/TRIG_4") (pintype "passive"))
      (node (ref "U12") (pin "8") (pinfunction "GND_8") (pintype "passive"))
      (node (ref "U13") (pin "2") (pinfunction "VSS_2") (pintype "power_in"))
      (node (ref "U2") (pin "1") (pinfunction "GND_1") (pintype "passive"))
      (node (ref "U2") (pin "11") (pinfunction "GND_11") (pintype "passive"))
      (node (ref "U2") (pin "14") (pinfunction "GND_14") (pintype "passive"))
      (node (ref "U2") (pin "2") (pinfunction "GND_2") (pintype "passive"))
      (node (ref "U2") (pin "36") (pinfunction "GND_36") (pintype "passive"))
      (node (ref "U2") (pin "37") (pinfunction "GND_37") (pintype "passive"))
      (node (ref "U2") (pin "38") (pinfunction "GND_38") (pintype "passive"))
      (node (ref "U2") (pin "39") (pinfunction "GND_39") (pintype "passive"))
      (node (ref "U2") (pin "40") (pinfunction "GND_40") (pintype "passive"))
      (node (ref "U2") (pin "41") (pinfunction "GND_41") (pintype "passive"))
      (node (ref "U2") (pin "42") (pinfunction "GND_42") (pintype "passive"))
      (node (ref "U2") (pin "43") (pinfunction "GND_43") (pintype "passive"))
      (node (ref "U2") (pin "44") (pinfunction "GND_44") (pintype "passive"))
      (node (ref "U2") (pin "45") (pinfunction "GND_45") (pintype "passive"))
      (node (ref "U2") (pin "46") (pinfunction "GND_46") (pintype "passive"))
      (node (ref "U2") (pin "47") (pinfunction "GND_47") (pintype "passive"))
      (node (ref "U2") (pin "48") (pinfunction "GND_48") (pintype "passive"))
      (node (ref "U2") (pin "49") (pinfunction "GND_49") (pintype "passive"))
      (node (ref "U2") (pin "50") (pinfunction "GND_50") (pintype "passive"))
      (node (ref "U2") (pin "51") (pinfunction "GND_51") (pintype "passive"))
      (node (ref "U2") (pin "52") (pinfunction "GND_52") (pintype "passive"))
      (node (ref "U2") (pin "53") (pinfunction "GND_53") (pintype "passive"))
      (node (ref "U2") (pin "54") (pinfunction "GND_54") (pintype "passive"))
      (node (ref "U2") (pin "55") (pinfunction "GND_55") (pintype "passive"))
      (node (ref "U2") (pin "56") (pinfunction "GND_56") (pintype "passive"))
      (node (ref "U2") (pin "57") (pinfunction "GND_57") (pintype "passive"))
      (node (ref "U2") (pin "58") (pinfunction "GND_58") (pintype "passive"))
      (node (ref "U2") (pin "59") (pinfunction "GND_59") (pintype "passive"))
      (node (ref "U2") (pin "60") (pinfunction "GND_60") (pintype "passive"))
      (node (ref "U2") (pin "61") (pinfunction "GND_61") (pintype "passive"))
      (node (ref "U3") (pin "1") (pinfunction "A0_1") (pintype "passive"))
      (node (ref "U3") (pin "12") (pinfunction "GND_12") (pintype "passive"))
      (node (ref "U3") (pin "2") (pinfunction "A1_2") (pintype "passive"))
      (node (ref "U3") (pin "21") (pinfunction "A2_21") (pintype "passive"))
      (node (ref "U4") (pin "2") (pinfunction "GND_2") (pintype "power_in"))
      (node (ref "U4") (pin "4") (pinfunction "GND_4") (pintype "power_in"))
      (node (ref "U5") (pin "4") (pinfunction "IN/TRIG_4") (pintype "passive"))
      (node (ref "U5") (pin "8") (pinfunction "GND_8") (pintype "passive"))
      (node (ref "U6") (pin "4") (pinfunction "IN/TRIG_4") (pintype "passive"))
      (node (ref "U6") (pin "8") (pinfunction "GND_8") (pintype "passive"))
      (node (ref "U7") (pin "4") (pinfunction "IN/TRIG_4") (pintype "passive"))
      (node (ref "U7") (pin "8") (pinfunction "GND_8") (pintype "passive"))
      (node (ref "U8") (pin "4") (pinfunction "IN/TRIG_4") (pintype "passive"))
      (node (ref "U8") (pin "8") (pinfunction "GND_8") (pintype "passive"))
      (node (ref "U9") (pin "4") (pinfunction "IN/TRIG_4") (pintype "passive"))
      (node (ref "U9") (pin "8") (pinfunction "GND_8") (pintype "passive"))
    )
    (net (code "30") (name "Net-(D1-A)") (class "Default")
      (node (ref "D1") (pin "2") (pinfunction "A_2") (pintype "passive"))
      (node (ref "D4") (pin "2") (pinfunction "K_2") (pintype "passive"))
      (node (ref "D4") (pin "K") (pinfunction "K_K") (pintype "passive"))
      (node (ref "J1") (pin "A4") (pinfunction "VBUS_A4") (pintype "passive"))
      (node (ref "J1") (pin "A9") (pinfunction "VBUS_A9") (pintype "passive"))
      (node (ref "J1") (pin "B4") (pinfunction "VBUS_B4") (pintype "passive"))
      (node (ref "J1") (pin "B9") (pinfunction "VBUS_B9") (pintype "passive"))
    )
    (net (code "31") (name "Net-(D6-PadA)") (class "Default")
      (node (ref "D6") (pin "A") (pinfunction "A_A") (pintype "passive"))
      (node (ref "R28") (pin "1") (pinfunction "1_1") (pintype "passive"))
    )
    (net (code "32") (name "Net-(D7-PadK)") (class "Default")
      (node (ref "D7") (pin "K") (pinfunction "K_K") (pintype "passive"))
      (node (ref "R32") (pin "1") (pinfunction "1_1") (pintype "passive"))
    )
    (net (code "33") (name "Net-(J1-CC1)") (class "Default")
      (node (ref "J1") (pin "A5") (pinfunction "CC1_A5") (pintype "passive"))
      (node (ref "R6") (pin "2") (pinfunction "2_2") (pintype "passive"))
    )
    (net (code "34") (name "Net-(J1-CC2)") (class "Default")
      (node (ref "J1") (pin "B5") (pinfunction "CC2_B5") (pintype "passive"))
      (node (ref "R5") (pin "2") (pinfunction "2_2") (pintype "passive"))
    )
    (net (code "35") (name "Net-(Q1-B)") (class "Default")
      (node (ref "Q1") (pin "1") (pinfunction "B_1") (pintype "passive"))
      (node (ref "R23") (pin "1") (pinfunction "1_1") (pintype "passive"))
    )
    (net (code "36") (name "Net-(Q2-B)") (class "Default")
      (node (ref "Q2") (pin "1") (pinfunction "B_1") (pintype "passive"))
      (node (ref "R25") (pin "1") (pinfunction "1_1") (pintype "passive"))
    )
    (net (code "37") (name "Net-(U1-VBUS)") (class "Default")
      (node (ref "R3") (pin "1") (pinfunction "1_1") (pintype "passive"))
      (node (ref "R4") (pin "2") (pinfunction "2_2") (pintype "passive"))
      (node (ref "U1") (pin "8") (pinfunction "VBUS_8") (pintype "passive"))
    )
    (net (code "38") (name "Net-(U1-~{RST})") (class "Default")
      (node (ref "R2") (pin "1") (pinfunction "1_1") (pintype "passive"))
      (node (ref "U1") (pin "9") (pinfunction "~{RST}_9") (pintype "passive"))
    )
    (net (code "39") (name "Net-(U3-~{RESET})") (class "Default")
      (node (ref "R24") (pin "1") (pinfunction "1_1") (pintype "passive"))
      (node (ref "U3") (pin "3") (pinfunction "~{RESET}_3") (pintype "passive"))
    )
    (net (code "40") (name "Net-(U5-OUT+)") (class "Default")
      (node (ref "J2") (pin "1") (pinfunction "1_1") (pintype "passive"))
      (node (ref "U5") (pin "7") (pinfunction "OUT+_7") (pintype "passive"))
    )
    (net (code "41") (name "Net-(U5-OUT-)") (class "Default")
      (node (ref "J2") (pin "2") (pinfunction "2_2") (pintype "passive"))
      (node (ref "U5") (pin "9") (pinfunction "OUT-_9") (pintype "passive"))
    )
    (net (code "42") (name "Net-(U5-REG)") (class "Default")
      (node (ref "C11") (pin "2") (pinfunction "2_2") (pintype "passive"))
      (node (ref "U5") (pin "1") (pinfunction "REG_1") (pintype "passive"))
    )
    (net (code "43") (name "Net-(U6-OUT+)") (class "Default")
      (node (ref "J3") (pin "1") (pinfunction "1_1") (pintype "passive"))
      (node (ref "U6") (pin "7") (pinfunction "OUT+_7") (pintype "passive"))
    )
    (net (code "44") (name "Net-(U6-OUT-)") (class "Default")
      (node (ref "J3") (pin "2") (pinfunction "2_2") (pintype "passive"))
      (node (ref "U6") (pin "9") (pinfunction "OUT-_9") (pintype "passive"))
    )
    (net (code "45") (name "Net-(U6-REG)") (class "Default")
      (node (ref "C13") (pin "2") (pinfunction "2_2") (pintype "passive"))
      (node (ref "U6") (pin "1") (pinfunction "REG_1") (pintype "passive"))
    )
    (net (code "46") (name "Net-(U7-OUT+)") (class "Default")
      (node (ref "J4") (pin "1") (pinfunction "1_1") (pintype "passive"))
      (node (ref "U7") (pin "7") (pinfunction "OUT+_7") (pintype "passive"))
    )
    (net (code "47") (name "Net-(U7-OUT-)") (class "Default")
      (node (ref "J4") (pin "2") (pinfunction "2_2") (pintype "passive"))
      (node (ref "U7") (pin "9") (pinfunction "OUT-_9") (pintype "passive"))
    )
    (net (code "48") (name "Net-(U7-REG)") (class "Default")
      (node (ref "C15") (pin "2") (pinfunction "2_2") (pintype "passive"))
      (node (ref "U7") (pin "1") (pinfunction "REG_1") (pintype "passive"))
    )
    (net (code "49") (name "Net-(U8-OUT+)") (class "Default")
      (node (ref "J5") (pin "1") (pinfunction "1_1") (pintype "passive"))
      (node (ref "U8") (pin "7") (pinfunction "OUT+_7") (pintype "passive"))
    )
    (net (code "50") (name "Net-(U8-OUT-)") (class "Default")
      (node (ref "J5") (pin "2") (pinfunction "2_2") (pintype "passive"))
      (node (ref "U8") (pin "9") (pinfunction "OUT-_9") (pintype "passive"))
    )
    (net (code "51") (name "Net-(U8-REG)") (class "Default")
      (node (ref "C17") (pin "2") (pinfunction "2_2") (pintype "passive"))
      (node (ref "U8") (pin "1") (pinfunction "REG_1") (pintype "passive"))
    )
    (net (code "52") (name "Net-(U9-OUT+)") (class "Default")
      (node (ref "J6") (pin "1") (pinfunction "1_1") (pintype "passive"))
      (node (ref "U9") (pin "7") (pinfunction "OUT+_7") (pintype "passive"))
    )
    (net (code "53") (name "Net-(U9-OUT-)") (class "Default")
      (node (ref "J6") (pin "2") (pinfunction "2_2") (pintype "passive"))
      (node (ref "U9") (pin "9") (pinfunction "OUT-_9") (pintype "passive"))
    )
    (net (code "54") (name "Net-(U9-REG)") (class "Default")
      (node (ref "C20") (pin "2") (pinfunction "2_2") (pintype "passive"))
      (node (ref "U9") (pin "1") (pinfunction "REG_1") (pintype "passive"))
    )
    (net (code "55") (name "Net-(U10-OUT+)") (class "Default")
      (node (ref "J7") (pin "1") (pinfunction "1_1") (pintype "passive"))
      (node (ref "U10") (pin "7") (pinfunction "OUT+_7") (pintype "passive"))
    )
    (net (code "56") (name "Net-(U10-OUT-)") (class "Default")
      (node (ref "J7") (pin "2") (pinfunction "2_2") (pintype "passive"))
      (node (ref "U10") (pin "9") (pinfunction "OUT-_9") (pintype "passive"))
    )
    (net (code "57") (name "Net-(U10-REG)") (class "Default")
      (node (ref "C22") (pin "2") (pinfunction "2_2") (pintype "passive"))
      (node (ref "U10") (pin "1") (pinfunction "REG_1") (pintype "passive"))
    )
    (net (code "58") (name "Net-(U11-OUT+)") (class "Default")
      (node (ref "J8") (pin "1") (pinfunction "1_1") (pintype "passive"))
      (node (ref "U11") (pin "7") (pinfunction "OUT+_7") (pintype "passive"))
    )
    (net (code "59") (name "Net-(U11-OUT-)") (class "Default")
      (node (ref "J8") (pin "2") (pinfunction "2_2") (pintype "passive"))
      (node (ref "U11") (pin "9") (pinfunction "OUT-_9") (pintype "passive"))
    )
    (net (code "60") (name "Net-(U11-REG)") (class "Default")
      (node (ref "C24") (pin "2") (pinfunction "2_2") (pintype "passive"))
      (node (ref "U11") (pin "1") (pinfunction "REG_1") (pintype "passive"))
    )
    (net (code "61") (name "Net-(U12-OUT+)") (class "Default")
      (node (ref "J9") (pin "1") (pinfunction "1_1") (pintype "passive"))
      (node (ref "U12") (pin "7") (pinfunction "OUT+_7") (pintype "passive"))
    )
    (net (code "62") (name "Net-(U12-OUT-)") (class "Default")
      (node (ref "J9") (pin "2") (pinfunction "2_2") (pintype "passive"))
      (node (ref "U12") (pin "9") (pinfunction "OUT-_9") (pintype "passive"))
    )
    (net (code "63") (name "Net-(U12-REG)") (class "Default")
      (node (ref "C26") (pin "2") (pinfunction "2_2") (pintype "passive"))
      (node (ref "U12") (pin "1") (pinfunction "REG_1") (pintype "passive"))
    )
    (net (code "64") (name "Net-(U13-PROG)") (class "Default")
      (node (ref "R33") (pin "2") (pinfunction "2_2") (pintype "passive"))
      (node (ref "U13") (pin "5") (pinfunction "PROG_5") (pintype "passive"))
    )
    (net (code "65") (name "Net-(U13-STAT)") (class "Default")
      (node (ref "R32") (pin "2") (pinfunction "2_2") (pintype "passive"))
      (node (ref "U13") (pin "1") (pinfunction "STAT_1") (pintype "passive"))
    )
    (net (code "66") (name "VCC_3V3") (class "Default")
      (node (ref "C10") (pin "2") (pinfunction "2_2") (pintype "passive"))
      (node (ref "C12") (pin "2") (pinfunction "2_2") (pintype "passive"))
      (node (ref "C14") (pin "2") (pinfunction "2_2") (pintype "passive"))
      (node (ref "C16") (pin "2") (pinfunction "2_2") (pintype "passive"))
      (node (ref "C19") (pin "2") (pinfunction "2_2") (pintype "passive"))
      (node (ref "C2") (pin "2") (pinfunction "2_2") (pintype "passive"))
      (node (ref "C21") (pin "2") (pinfunction "2_2") (pintype "passive"))
      (node (ref "C23") (pin "2") (pinfunction "2_2") (pintype "passive"))
      (node (ref "C25") (pin "2") (pinfunction "2_2") (pintype "passive"))
      (node (ref "C3") (pin "2") (pinfunction "2_2") (pintype "passive"))
      (node (ref "C4") (pin "2") (pinfunction "2_2") (pintype "passive"))
      (node (ref "C5") (pin "2") (pinfunction "2_2") (pintype "passive"))
      (node (ref "C7") (pin "2") (pinfunction "2_2") (pintype "passive"))
      (node (ref "C8") (pin "2") (pinfunction "2_2") (pintype "passive"))
      (node (ref "R1") (pin "2") (pinfunction "2_2") (pintype "passive"))
      (node (ref "R10") (pin "2") (pinfunction "2_2") (pintype "passive"))
      (node (ref "R11") (pin "2") (pinfunction "2_2") (pintype "passive"))
      (node (ref "R12") (pin "2") (pinfunction "2_2") (pintype "passive"))
      (node (ref "R13") (pin "2") (pinfunction "2_2") (pintype "passive"))
      (node (ref "R14") (pin "2") (pinfunction "2_2") (pintype "passive"))
      (node (ref "R15") (pin "2") (pinfunction "2_2") (pintype "passive"))
      (node (ref "R16") (pin "2") (pinfunction "2_2") (pintype "passive"))
      (node (ref "R17") (pin "2") (pinfunction "2_2") (pintype "passive"))
      (node (ref "R18") (pin "2") (pinfunction "2_2") (pintype "passive"))
      (node (ref "R19") (pin "2") (pinfunction "2_2") (pintype "passive"))
      (node (ref "R2") (pin "2") (pinfunction "2_2") (pintype "passive"))
      (node (ref "R20") (pin "2") (pinfunction "2_2") (pintype "passive"))
      (node (ref "R21") (pin "2") (pinfunction "2_2") (pintype "passive"))
      (node (ref "R22") (pin "2") (pinfunction "2_2") (pintype "passive"))
      (node (ref "R24") (pin "2") (pinfunction "2_2") (pintype "passive"))
      (node (ref "R26") (pin "2") (pinfunction "2_2") (pintype "passive"))
      (node (ref "R27") (pin "2") (pinfunction "2_2") (pintype "passive"))
      (node (ref "R28") (pin "2") (pinfunction "2_2") (pintype "passive"))
      (node (ref "R29") (pin "2") (pinfunction "2_2") (pintype "passive"))
      (node (ref "R30") (pin "2") (pinfunction "2_2") (pintype "passive"))
      (node (ref "R7") (pin "2") (pinfunction "2_2") (pintype "passive"))
      (node (ref "R8") (pin "2") (pinfunction "2_2") (pintype "passive"))
      (node (ref "R9") (pin "2") (pinfunction "2_2") (pintype "passive"))
      (node (ref "U1") (pin "6") (pinfunction "VDD_6") (pintype "passive"))
      (node (ref "U1") (pin "7") (pinfunction "VREGIN_7") (pintype "passive"))
      (node (ref "U10") (pin "10") (pinfunction "VDD_10") (pintype "passive"))
      (node (ref "U10") (pin "5") (pinfunction "EN_5") (pintype "passive"))
      (node (ref "U10") (pin "6") (pinfunction "VDD/NC_6") (pintype "passive"))
      (node (ref "U11") (pin "10") (pinfunction "VDD_10") (pintype "passive"))
      (node (ref "U11") (pin "5") (pinfunction "EN_5") (pintype "passive"))
      (node (ref "U11") (pin "6") (pinfunction "VDD/NC_6") (pintype "passive"))
      (node (ref "U12") (pin "10") (pinfunction "VDD_10") (pintype "passive"))
      (node (ref "U12") (pin "5") (pinfunction "EN_5") (pintype "passive"))
      (node (ref "U12") (pin "6") (pinfunction "VDD/NC_6") (pintype "passive"))
      (node (ref "U2") (pin "3") (pinfunction "3V3_3") (pintype "passive"))
      (node (ref "U3") (pin "24") (pinfunction "VCC_24") (pintype "passive"))
      (node (ref "U4") (pin "3") (pinfunction "OUT_3") (pintype "power_in"))
      (node (ref "U5") (pin "10") (pinfunction "VDD_10") (pintype "passive"))
      (node (ref "U5") (pin "5") (pinfunction "EN_5") (pintype "passive"))
      (node (ref "U5") (pin "6") (pinfunction "VDD/NC_6") (pintype "passive"))
      (node (ref "U6") (pin "10") (pinfunction "VDD_10") (pintype "passive"))
      (node (ref "U6") (pin "5") (pinfunction "EN_5") (pintype "passive"))
      (node (ref "U6") (pin "6") (pinfunction "VDD/NC_6") (pintype "passive"))
      (node (ref "U7") (pin "10") (pinfunction "VDD_10") (pintype "passive"))
      (node (ref "U7") (pin "5") (pinfunction "EN_5") (pintype "passive"))
      (node (ref "U7") (pin "6") (pinfunction "VDD/NC_6") (pintype "passive"))
      (node (ref "U8") (pin "10") (pinfunction "VDD_10") (pintype "passive"))
      (node (ref "U8") (pin "5") (pinfunction "EN_5") (pintype "passive"))
      (node (ref "U8") (pin "6") (pinfunction "VDD/NC_6") (pintype "passive"))
      (node (ref "U9") (pin "10") (pinfunction "VDD_10") (pintype "passive"))
      (node (ref "U9") (pin "5") (pinfunction "EN_5") (pintype "passive"))
      (node (ref "U9") (pin "6") (pinfunction "VDD/NC_6") (pintype "passive"))
    )
    (net (code "67") (name "VCC_5V") (class "Default")
      (node (ref "C6") (pin "2") (pinfunction "2_2") (pintype "passive"))
      (node (ref "D5") (pin "1") (pinfunction "C_1") (pintype "passive"))
      (node (ref "Q3") (pin "2") (pinfunction "S_2") (pintype "passive"))
      (node (ref "U4") (pin "1") (pinfunction "IN_1") (pintype "power_in"))
    )
    (net (code "68") (name "VCC_BATT") (class "Default")
      (node (ref "C18") (pin "1") (pinfunction "1_1") (pintype "passive"))
      (node (ref "Q3") (pin "3") (pinfunction "D_3") (pintype "passive"))
      (node (ref "U13") (pin "3") (pinfunction "VBAT_3") (pintype "power_in"))
    )
    (net (code "69") (name "VCC_USB") (class "Default")
      (node (ref "C9") (pin "1") (pinfunction "1_1") (pintype "passive"))
      (node (ref "D1") (pin "1") (pinfunction "C_1") (pintype "passive"))
      (node (ref "D5") (pin "2") (pinfunction "A_2") (pintype "passive"))
      (node (ref "D7") (pin "A") (pinfunction "A_A") (pintype "passive"))
      (node (ref "Q3") (pin "1") (pinfunction "G_1") (pintype "passive"))
      (node (ref "R3") (pin "2") (pinfunction "2_2") (pintype "passive"))
      (node (ref "R31") (pin "2") (pinfunction "2_2") (pintype "passive"))
      (node (ref "U13") (pin "4") (pinfunction "VDD_4") (pintype "power_in"))
    )
    (net (code "70") (name "unconnected-(J1-RX1+-PadB11)") (class "Default")
      (node (ref "J1") (pin "B11") (pinfunction "RX1+_B11") (pintype "passive+no_connect"))
    )
    (net (code "71") (name "unconnected-(J1-RX1--PadB10)") (class "Default")
      (node (ref "J1") (pin "B10") (pinfunction "RX1-_B10") (pintype "passive+no_connect"))
    )
    (net (code "72") (name "unconnected-(J1-RX2+-PadA11)") (class "Default")
      (node (ref "J1") (pin "A11") (pinfunction "RX2+_A11") (pintype "passive+no_connect"))
    )
    (net (code "73") (name "unconnected-(J1-RX2--PadA10)") (class "Default")
      (node (ref "J1") (pin "A10") (pinfunction "RX2-_A10") (pintype "passive+no_connect"))
    )
    (net (code "74") (name "unconnected-(J1-SBU1-PadA8)") (class "Default")
      (node (ref "J1") (pin "A8") (pinfunction "SBU1_A8") (pintype "passive+no_connect"))
    )
    (net (code "75") (name "unconnected-(J1-SBU2-PadB8)") (class "Default")
      (node (ref "J1") (pin "B8") (pinfunction "SBU2_B8") (pintype "passive+no_connect"))
    )
    (net (code "76") (name "unconnected-(J1-TX1+-PadA2)") (class "Default")
      (node (ref "J1") (pin "A2") (pinfunction "TX1+_A2") (pintype "passive+no_connect"))
    )
    (net (code "77") (name "unconnected-(J1-TX1--PadA3)") (class "Default")
      (node (ref "J1") (pin "A3") (pinfunction "TX1-_A3") (pintype "passive+no_connect"))
    )
    (net (code "78") (name "unconnected-(J1-TX2+-PadB2)") (class "Default")
      (node (ref "J1") (pin "B2") (pinfunction "TX2+_B2") (pintype "passive+no_connect"))
    )
    (net (code "79") (name "unconnected-(J1-TX2--PadB3)") (class "Default")
      (node (ref "J1") (pin "B3") (pinfunction "TX2-_B3") (pintype "passive+no_connect"))
    )
    (net (code "80") (name "unconnected-(SW1-NO-Pad1)") (class "Default")
      (node (ref "SW1") (pin "1") (pinfunction "NO_1") (pintype "passive+no_connect"))
    )
    (net (code "81") (name "unconnected-(SW1-NO-Pad2)") (class "Default")
      (node (ref "SW1") (pin "2") (pinfunction "NO_2") (pintype "passive+no_connect"))
    )
    (net (code "82") (name "unconnected-(SW2-NO-Pad1)") (class "Default")
      (node (ref "SW2") (pin "1") (pinfunction "NO_1") (pintype "passive+no_connect"))
    )
    (net (code "83") (name "unconnected-(SW2-NO-Pad2)") (class "Default")
      (node (ref "SW2") (pin "2") (pinfunction "NO_2") (pintype "passive+no_connect"))
    )
    (net (code "84") (name "unconnected-(U1-CHR0-Pad15)") (class "Default")
      (node (ref "U1") (pin "15") (pinfunction "CHR0_15") (pintype "passive+no_connect"))
    )
    (net (code "85") (name "unconnected-(U1-CHR1-Pad14)") (class "Default")
      (node (ref "U1") (pin "14") (pinfunction "CHR1_14") (pintype "passive+no_connect"))
    )
    (net (code "86") (name "unconnected-(U1-CHREN-Pad13)") (class "Default")
      (node (ref "U1") (pin "13") (pinfunction "CHREN_13") (pintype "passive+no_connect"))
    )
    (net (code "87") (name "unconnected-(U1-CTS-Pad23)") (class "Default")
      (node (ref "U1") (pin "23") (pinfunction "CTS_23") (pintype "passive+no_connect"))
    )
    (net (code "88") (name "unconnected-(U1-DCD-Pad1)") (class "Default")
      (node (ref "U1") (pin "1") (pinfunction "DCD_1") (pintype "passive+no_connect"))
    )
    (net (code "89") (name "unconnected-(U1-DSR-Pad27)") (class "Default")
      (node (ref "U1") (pin "27") (pinfunction "DSR_27") (pintype "passive+no_connect"))
    )
    (net (code "90") (name "unconnected-(U1-GPIO.0{slash}TXT-Pad19)") (class "Default")
      (node (ref "U1") (pin "19") (pinfunction "GPIO.0/TXT_19") (pintype "passive+no_connect"))
    )
    (net (code "91") (name "unconnected-(U1-GPIO.1{slash}RXT-Pad18)") (class "Default")
      (node (ref "U1") (pin "18") (pinfunction "GPIO.1/RXT_18") (pintype "passive+no_connect"))
    )
    (net (code "92") (name "unconnected-(U1-GPIO.2{slash}RS485-Pad17)") (class "Default")
      (node (ref "U1") (pin "17") (pinfunction "GPIO.2/RS485_17") (pintype "passive+no_connect"))
    )
    (net (code "93") (name "unconnected-(U1-GPIO.3{slash}WAKEUP-Pad16)") (class "Default")
      (node (ref "U1") (pin "16") (pinfunction "GPIO.3/WAKEUP_16") (pintype "passive+no_connect"))
    )
    (net (code "94") (name "unconnected-(U1-GPIO.4-Pad22)") (class "Default")
      (node (ref "U1") (pin "22") (pinfunction "GPIO.4_22") (pintype "passive+no_connect"))
    )
    (net (code "95") (name "unconnected-(U1-GPIO.5-Pad21)") (class "Default")
      (node (ref "U1") (pin "21") (pinfunction "GPIO.5_21") (pintype "passive+no_connect"))
    )
    (net (code "96") (name "unconnected-(U1-GPIO.6-Pad20)") (class "Default")
      (node (ref "U1") (pin "20") (pinfunction "GPIO.6_20") (pintype "passive+no_connect"))
    )
    (net (code "97") (name "unconnected-(U1-NC-Pad10)") (class "Default")
      (node (ref "U1") (pin "10") (pinfunction "NC_10") (pintype "passive+no_connect"))
    )
    (net (code "98") (name "unconnected-(U1-SUSPEND-Pad12)") (class "Default")
      (node (ref "U1") (pin "12") (pinfunction "SUSPEND_12") (pintype "passive+no_connect"))
    )
    (net (code "99") (name "unconnected-(U1-~{RI}{slash}CLK-Pad2)") (class "Default")
      (node (ref "U1") (pin "2") (pinfunction "~{RI}/CLK_2") (pintype "passive+no_connect"))
    )
    (net (code "100") (name "unconnected-(U1-~{SUSPEND}-Pad11)") (class "Default")
      (node (ref "U1") (pin "11") (pinfunction "~{SUSPEND}_11") (pintype "passive+no_connect"))
    )
    (net (code "101") (name "unconnected-(U2-GPIO0{slash}ADC1_CH0{slash}XTAL_32K_P-Pad12)") (class "Default")
      (node (ref "U2") (pin "12") (pinfunction "GPIO0/ADC1_CH0/XTAL_32K_P_12") (pintype "passive+no_connect"))
    )
    (net (code "102") (name "unconnected-(U2-GPIO1{slash}ADC1_CH1{slash}XTAL_32K_N-Pad13)") (class "Default")
      (node (ref "U2") (pin "13") (pinfunction "GPIO1/ADC1_CH1/XTAL_32K_N_13") (pintype "passive+no_connect"))
    )
    (net (code "103") (name "unconnected-(U2-GPIO3{slash}ADC1_CH3-Pad6)") (class "Default")
      (node (ref "U2") (pin "6") (pinfunction "GPIO3/ADC1_CH3_6") (pintype "passive+no_connect"))
    )
    (net (code "104") (name "unconnected-(U2-GPIO4{slash}ADC1_CH4{slash}FSPIHD{slash}MTMS-Pad18)") (class "Default")
      (node (ref "U2") (pin "18") (pinfunction "GPIO4/ADC1_CH4/FSPIHD/MTMS_18") (pintype "passive+no_connect"))
    )
    (net (code "105") (name "unconnected-(U2-GPIO5{slash}ADC2_CH0{slash}FSPIWP{slash}MTDI-Pad19)") (class "Default")
      (node (ref "U2") (pin "19") (pinfunction "GPIO5/ADC2_CH0/FSPIWP/MTDI_19") (pintype "passive+no_connect"))
    )
    (net (code "106") (name "unconnected-(U2-GPIO10{slash}FSPICS0-Pad16)") (class "Default")
      (node (ref "U2") (pin "16") (pinfunction "GPIO10/FSPICS0_16") (pintype "passive+no_connect"))
    )
    (net (code "107") (name "unconnected-(U2-GPIO18{slash}USB_D--Pad26)") (class "Default")
      (node (ref "U2") (pin "26") (pinfunction "GPIO18/USB_D-_26") (pintype "passive+no_connect"))
    )
    (net (code "108") (name "unconnected-(U2-GPIO19{slash}USB_D+-Pad27)") (class "Default")
      (node (ref "U2") (pin "27") (pinfunction "GPIO19/USB_D+_27") (pintype "passive+no_connect"))
    )
    (net (code "109") (name "unconnected-(U2-NC-Pad4)") (class "Default")
      (node (ref "U2") (pin "4") (pinfunction "NC_4") (pintype "passive+no_connect"))
    )
    (net (code "110") (name "unconnected-(U2-NC-Pad7)") (class "Default")
      (node (ref "U2") (pin "7") (pinfunction "NC_7") (pintype "passive+no_connect"))
    )
    (net (code "111") (name "unconnected-(U2-NC-Pad9)") (class "Default")
      (node (ref "U2") (pin "9") (pinfunction "NC_9") (pintype "passive+no_connect"))
    )
    (net (code "112") (name "unconnected-(U2-NC-Pad10)") (class "Default")
      (node (ref "U2") (pin "10") (pinfunction "NC_10") (pintype "passive+no_connect"))
    )
    (net (code "113") (name "unconnected-(U2-NC-Pad15)") (class "Default")
      (node (ref "U2") (pin "15") (pinfunction "NC_15") (pintype "passive+no_connect"))
    )
    (net (code "114") (name "unconnected-(U2-NC-Pad17)") (class "Default")
      (node (ref "U2") (pin "17") (pinfunction "NC_17") (pintype "passive+no_connect"))
    )
    (net (code "115") (name "unconnected-(U2-NC-Pad24)") (class "Default")
      (node (ref "U2") (pin "24") (pinfunction "NC_24") (pintype "passive+no_connect"))
    )
    (net (code "116") (name "unconnected-(U2-NC-Pad25)") (class "Default")
      (node (ref "U2") (pin "25") (pinfunction "NC_25") (pintype "passive+no_connect"))
    )
    (net (code "117") (name "unconnected-(U2-NC-Pad28)") (class "Default")
      (node (ref "U2") (pin "28") (pinfunction "NC_28") (pintype "passive+no_connect"))
    )
    (net (code "118") (name "unconnected-(U2-NC-Pad29)") (class "Default")
      (node (ref "U2") (pin "29") (pinfunction "NC_29") (pintype "passive+no_connect"))
    )
    (net (code "119") (name "unconnected-(U2-NC-Pad32)") (class "Default")
      (node (ref "U2") (pin "32") (pinfunction "NC_32") (pintype "passive+no_connect"))
    )
    (net (code "120") (name "unconnected-(U2-NC-Pad33)") (class "Default")
      (node (ref "U2") (pin "33") (pinfunction "NC_33") (pintype "passive+no_connect"))
    )
    (net (code "121") (name "unconnected-(U2-NC-Pad34)") (class "Default")
      (node (ref "U2") (pin "34") (pinfunction "NC_34") (pintype "passive+no_connect"))
    )
    (net (code "122") (name "unconnected-(U2-NC-Pad35)") (class "Default")
      (node (ref "U2") (pin "35") (pinfunction "NC_35") (pintype "passive+no_connect"))
    )
  )
)
